# Xilinx_pwr.net
KiCad netlist of a schematic drawn in Altium Designer
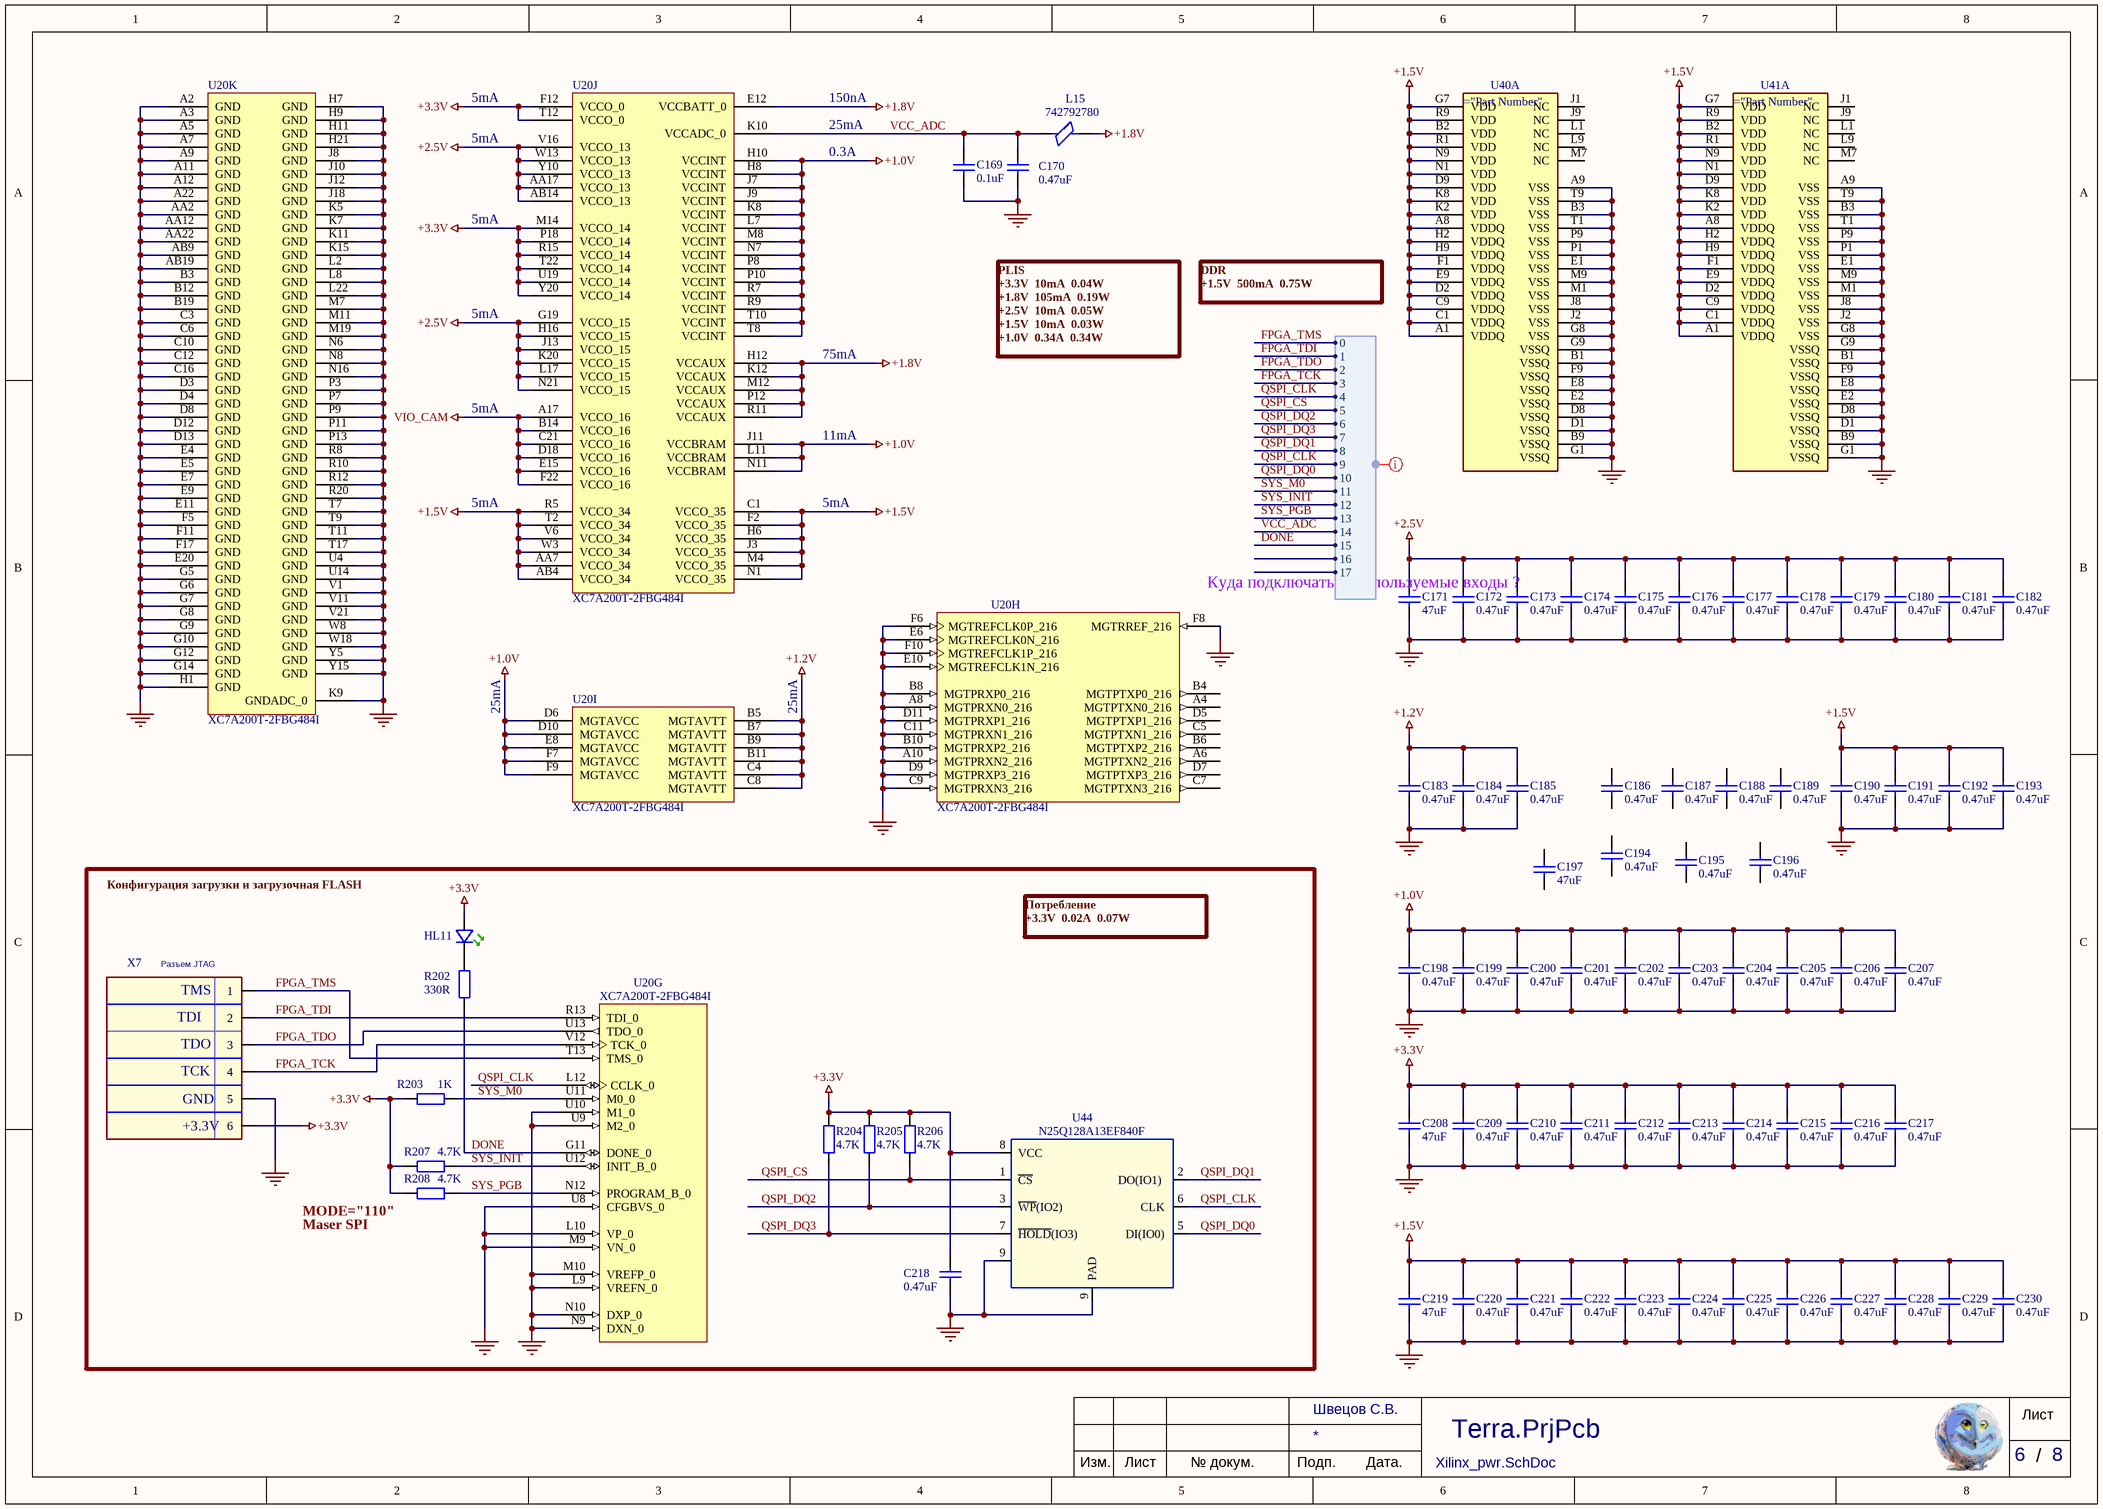
[diagram p0: Xilinx_pwr.SchDoc]

(export (version "E")
  (design (tool "Eeschema 10.0.6"))
  (components
    (comp (ref "C169")
      (value "0.1uF")
      (footprint "C0402")
      (description "Конденсатор керамический")
      (fields (field (name "VOLTAGE") "25V") (field (name "Comment") "Cap"))
      (libsource (lib "Terra") (part "Cap"))
    )
    (comp (ref "C170")
      (value "0.47uF")
      (footprint "C0402")
      (description "Конденсатор керамический")
      (fields (field (name "VOLTAGE") "10V") (field (name "Comment") "Cap"))
      (libsource (lib "Terra") (part "Cap"))
    )
    (comp (ref "C171")
      (value "47uF")
      (footprint "C0805")
      (description "C0805C476M9PAC")
      (fields (field (name "VOLTAGE") "6.3V") (field (name "Comment") "Cap"))
      (libsource (lib "Terra") (part "Cap"))
    )
    (comp (ref "C172")
      (value "0.47uF")
      (footprint "C0402")
      (description "Конденсатор керамический")
      (fields (field (name "VOLTAGE") "10V") (field (name "Comment") "Cap"))
      (libsource (lib "Terra") (part "Cap"))
    )
    (comp (ref "C173")
      (value "0.47uF")
      (footprint "C0402")
      (description "Конденсатор керамический")
      (fields (field (name "VOLTAGE") "10V") (field (name "Comment") "Cap"))
      (libsource (lib "Terra") (part "Cap"))
    )
    (comp (ref "C174")
      (value "0.47uF")
      (footprint "C0402")
      (description "Конденсатор керамический")
      (fields (field (name "VOLTAGE") "10V") (field (name "Comment") "Cap"))
      (libsource (lib "Terra") (part "Cap"))
    )
    (comp (ref "C175")
      (value "0.47uF")
      (footprint "C0402")
      (description "Конденсатор керамический")
      (fields (field (name "VOLTAGE") "10V") (field (name "Comment") "Cap"))
      (libsource (lib "Terra") (part "Cap"))
    )
    (comp (ref "C176")
      (value "0.47uF")
      (footprint "C0402")
      (description "Конденсатор керамический")
      (fields (field (name "VOLTAGE") "10V") (field (name "Comment") "Cap"))
      (libsource (lib "Terra") (part "Cap"))
    )
    (comp (ref "C177")
      (value "0.47uF")
      (footprint "C0402")
      (description "Конденсатор керамический")
      (fields (field (name "VOLTAGE") "10V") (field (name "Comment") "Cap"))
      (libsource (lib "Terra") (part "Cap"))
    )
    (comp (ref "C178")
      (value "0.47uF")
      (footprint "C0402")
      (description "Конденсатор керамический")
      (fields (field (name "VOLTAGE") "10V") (field (name "Comment") "Cap"))
      (libsource (lib "Terra") (part "Cap"))
    )
    (comp (ref "C179")
      (value "0.47uF")
      (footprint "C0402")
      (description "Конденсатор керамический")
      (fields (field (name "VOLTAGE") "10V") (field (name "Comment") "Cap"))
      (libsource (lib "Terra") (part "Cap"))
    )
    (comp (ref "C180")
      (value "0.47uF")
      (footprint "C0402")
      (description "Конденсатор керамический")
      (fields (field (name "VOLTAGE") "10V") (field (name "Comment") "Cap"))
      (libsource (lib "Terra") (part "Cap"))
    )
    (comp (ref "C181")
      (value "0.47uF")
      (footprint "C0402")
      (description "Конденсатор керамический")
      (fields (field (name "VOLTAGE") "10V") (field (name "Comment") "Cap"))
      (libsource (lib "Terra") (part "Cap"))
    )
    (comp (ref "C182")
      (value "0.47uF")
      (footprint "C0402")
      (description "Конденсатор керамический")
      (fields (field (name "VOLTAGE") "10V") (field (name "Comment") "Cap"))
      (libsource (lib "Terra") (part "Cap"))
    )
    (comp (ref "C183")
      (value "0.47uF")
      (footprint "C0402")
      (description "Конденсатор керамический")
      (fields (field (name "VOLTAGE") "10V") (field (name "Comment") "Cap"))
      (libsource (lib "Terra") (part "Cap"))
    )
    (comp (ref "C184")
      (value "0.47uF")
      (footprint "C0402")
      (description "Конденсатор керамический")
      (fields (field (name "VOLTAGE") "10V") (field (name "Comment") "Cap"))
      (libsource (lib "Terra") (part "Cap"))
    )
    (comp (ref "C185")
      (value "0.47uF")
      (footprint "C0402")
      (description "Конденсатор керамический")
      (fields (field (name "VOLTAGE") "10V") (field (name "Comment") "Cap"))
      (libsource (lib "Terra") (part "Cap"))
    )
    (comp (ref "C186")
      (value "0.47uF")
      (footprint "C0402")
      (description "Конденсатор керамический")
      (fields (field (name "VOLTAGE") "10V") (field (name "Comment") "Cap"))
      (libsource (lib "Terra") (part "Cap"))
    )
    (comp (ref "C187")
      (value "0.47uF")
      (footprint "C0402")
      (description "Конденсатор керамический")
      (fields (field (name "VOLTAGE") "10V") (field (name "Comment") "Cap"))
      (libsource (lib "Terra") (part "Cap"))
    )
    (comp (ref "C188")
      (value "0.47uF")
      (footprint "C0402")
      (description "Конденсатор керамический")
      (fields (field (name "VOLTAGE") "10V") (field (name "Comment") "Cap"))
      (libsource (lib "Terra") (part "Cap"))
    )
    (comp (ref "C189")
      (value "0.47uF")
      (footprint "C0402")
      (description "Конденсатор керамический")
      (fields (field (name "VOLTAGE") "10V") (field (name "Comment") "Cap"))
      (libsource (lib "Terra") (part "Cap"))
    )
    (comp (ref "C190")
      (value "0.47uF")
      (footprint "C0402")
      (description "Конденсатор керамический")
      (fields (field (name "VOLTAGE") "10V") (field (name "Comment") "Cap"))
      (libsource (lib "Terra") (part "Cap"))
    )
    (comp (ref "C191")
      (value "0.47uF")
      (footprint "C0402")
      (description "Конденсатор керамический")
      (fields (field (name "VOLTAGE") "10V") (field (name "Comment") "Cap"))
      (libsource (lib "Terra") (part "Cap"))
    )
    (comp (ref "C192")
      (value "0.47uF")
      (footprint "C0402")
      (description "Конденсатор керамический")
      (fields (field (name "VOLTAGE") "10V") (field (name "Comment") "Cap"))
      (libsource (lib "Terra") (part "Cap"))
    )
    (comp (ref "C193")
      (value "0.47uF")
      (footprint "C0402")
      (description "Конденсатор керамический")
      (fields (field (name "VOLTAGE") "10V") (field (name "Comment") "Cap"))
      (libsource (lib "Terra") (part "Cap"))
    )
    (comp (ref "C194")
      (value "0.47uF")
      (footprint "C0402")
      (description "Конденсатор керамический")
      (fields (field (name "VOLTAGE") "10V") (field (name "Comment") "Cap"))
      (libsource (lib "Terra") (part "Cap"))
    )
    (comp (ref "C195")
      (value "0.47uF")
      (footprint "C0402")
      (description "Конденсатор керамический")
      (fields (field (name "VOLTAGE") "10V") (field (name "Comment") "Cap"))
      (libsource (lib "Terra") (part "Cap"))
    )
    (comp (ref "C196")
      (value "0.47uF")
      (footprint "C0402")
      (description "Конденсатор керамический")
      (fields (field (name "VOLTAGE") "10V") (field (name "Comment") "Cap"))
      (libsource (lib "Terra") (part "Cap"))
    )
    (comp (ref "C197")
      (value "47uF")
      (footprint "C0805")
      (description "C0805C476M9PAC")
      (fields (field (name "VOLTAGE") "6.3V") (field (name "Comment") "Cap"))
      (libsource (lib "Terra") (part "Cap"))
    )
    (comp (ref "C198")
      (value "0.47uF")
      (footprint "C0402")
      (description "Конденсатор керамический")
      (fields (field (name "VOLTAGE") "10V") (field (name "Comment") "Cap"))
      (libsource (lib "Terra") (part "Cap"))
    )
    (comp (ref "C199")
      (value "0.47uF")
      (footprint "C0402")
      (description "Конденсатор керамический")
      (fields (field (name "VOLTAGE") "10V") (field (name "Comment") "Cap"))
      (libsource (lib "Terra") (part "Cap"))
    )
    (comp (ref "C200")
      (value "0.47uF")
      (footprint "C0402")
      (description "Конденсатор керамический")
      (fields (field (name "VOLTAGE") "10V") (field (name "Comment") "Cap"))
      (libsource (lib "Terra") (part "Cap"))
    )
    (comp (ref "C201")
      (value "0.47uF")
      (footprint "C0402")
      (description "Конденсатор керамический")
      (fields (field (name "VOLTAGE") "10V") (field (name "Comment") "Cap"))
      (libsource (lib "Terra") (part "Cap"))
    )
    (comp (ref "C202")
      (value "0.47uF")
      (footprint "C0402")
      (description "Конденсатор керамический")
      (fields (field (name "VOLTAGE") "10V") (field (name "Comment") "Cap"))
      (libsource (lib "Terra") (part "Cap"))
    )
    (comp (ref "C203")
      (value "0.47uF")
      (footprint "C0402")
      (description "Конденсатор керамический")
      (fields (field (name "VOLTAGE") "10V") (field (name "Comment") "Cap"))
      (libsource (lib "Terra") (part "Cap"))
    )
    (comp (ref "C204")
      (value "0.47uF")
      (footprint "C0402")
      (description "Конденсатор керамический")
      (fields (field (name "VOLTAGE") "10V") (field (name "Comment") "Cap"))
      (libsource (lib "Terra") (part "Cap"))
    )
    (comp (ref "C205")
      (value "0.47uF")
      (footprint "C0402")
      (description "Конденсатор керамический")
      (fields (field (name "VOLTAGE") "10V") (field (name "Comment") "Cap"))
      (libsource (lib "Terra") (part "Cap"))
    )
    (comp (ref "C206")
      (value "0.47uF")
      (footprint "C0402")
      (description "Конденсатор керамический")
      (fields (field (name "VOLTAGE") "10V") (field (name "Comment") "Cap"))
      (libsource (lib "Terra") (part "Cap"))
    )
    (comp (ref "C207")
      (value "0.47uF")
      (footprint "C0402")
      (description "Конденсатор керамический")
      (fields (field (name "VOLTAGE") "10V") (field (name "Comment") "Cap"))
      (libsource (lib "Terra") (part "Cap"))
    )
    (comp (ref "C208")
      (value "47uF")
      (footprint "C0805")
      (description "C0805C476M9PAC")
      (fields (field (name "VOLTAGE") "6.3V") (field (name "Comment") "Cap"))
      (libsource (lib "Terra") (part "Cap"))
    )
    (comp (ref "C209")
      (value "0.47uF")
      (footprint "C0402")
      (description "Конденсатор керамический")
      (fields (field (name "VOLTAGE") "10V") (field (name "Comment") "Cap"))
      (libsource (lib "Terra") (part "Cap"))
    )
    (comp (ref "C210")
      (value "0.47uF")
      (footprint "C0402")
      (description "Конденсатор керамический")
      (fields (field (name "VOLTAGE") "10V") (field (name "Comment") "Cap"))
      (libsource (lib "Terra") (part "Cap"))
    )
    (comp (ref "C211")
      (value "0.47uF")
      (footprint "C0402")
      (description "Конденсатор керамический")
      (fields (field (name "VOLTAGE") "10V") (field (name "Comment") "Cap"))
      (libsource (lib "Terra") (part "Cap"))
    )
    (comp (ref "C212")
      (value "0.47uF")
      (footprint "C0402")
      (description "Конденсатор керамический")
      (fields (field (name "VOLTAGE") "10V") (field (name "Comment") "Cap"))
      (libsource (lib "Terra") (part "Cap"))
    )
    (comp (ref "C213")
      (value "0.47uF")
      (footprint "C0402")
      (description "Конденсатор керамический")
      (fields (field (name "VOLTAGE") "10V") (field (name "Comment") "Cap"))
      (libsource (lib "Terra") (part "Cap"))
    )
    (comp (ref "C214")
      (value "0.47uF")
      (footprint "C0402")
      (description "Конденсатор керамический")
      (fields (field (name "VOLTAGE") "10V") (field (name "Comment") "Cap"))
      (libsource (lib "Terra") (part "Cap"))
    )
    (comp (ref "C215")
      (value "0.47uF")
      (footprint "C0402")
      (description "Конденсатор керамический")
      (fields (field (name "VOLTAGE") "10V") (field (name "Comment") "Cap"))
      (libsource (lib "Terra") (part "Cap"))
    )
    (comp (ref "C216")
      (value "0.47uF")
      (footprint "C0402")
      (description "Конденсатор керамический")
      (fields (field (name "VOLTAGE") "10V") (field (name "Comment") "Cap"))
      (libsource (lib "Terra") (part "Cap"))
    )
    (comp (ref "C217")
      (value "0.47uF")
      (footprint "C0402")
      (description "Конденсатор керамический")
      (fields (field (name "VOLTAGE") "10V") (field (name "Comment") "Cap"))
      (libsource (lib "Terra") (part "Cap"))
    )
    (comp (ref "C218")
      (value "0.47uF")
      (footprint "C0402")
      (description "Конденсатор керамический")
      (fields (field (name "VOLTAGE") "10V") (field (name "Comment") "Cap"))
      (libsource (lib "Terra") (part "Cap"))
    )
    (comp (ref "C219")
      (value "47uF")
      (footprint "C0805")
      (description "C0805C476M9PAC")
      (fields (field (name "VOLTAGE") "6.3V") (field (name "Comment") "Cap"))
      (libsource (lib "Terra") (part "Cap"))
    )
    (comp (ref "C220")
      (value "0.47uF")
      (footprint "C0402")
      (description "Конденсатор керамический")
      (fields (field (name "VOLTAGE") "10V") (field (name "Comment") "Cap"))
      (libsource (lib "Terra") (part "Cap"))
    )
    (comp (ref "C221")
      (value "0.47uF")
      (footprint "C0402")
      (description "Конденсатор керамический")
      (fields (field (name "VOLTAGE") "10V") (field (name "Comment") "Cap"))
      (libsource (lib "Terra") (part "Cap"))
    )
    (comp (ref "C222")
      (value "0.47uF")
      (footprint "C0402")
      (description "Конденсатор керамический")
      (fields (field (name "VOLTAGE") "10V") (field (name "Comment") "Cap"))
      (libsource (lib "Terra") (part "Cap"))
    )
    (comp (ref "C223")
      (value "0.47uF")
      (footprint "C0402")
      (description "Конденсатор керамический")
      (fields (field (name "VOLTAGE") "10V") (field (name "Comment") "Cap"))
      (libsource (lib "Terra") (part "Cap"))
    )
    (comp (ref "C224")
      (value "0.47uF")
      (footprint "C0402")
      (description "Конденсатор керамический")
      (fields (field (name "VOLTAGE") "10V") (field (name "Comment") "Cap"))
      (libsource (lib "Terra") (part "Cap"))
    )
    (comp (ref "C225")
      (value "0.47uF")
      (footprint "C0402")
      (description "Конденсатор керамический")
      (fields (field (name "VOLTAGE") "10V") (field (name "Comment") "Cap"))
      (libsource (lib "Terra") (part "Cap"))
    )
    (comp (ref "C226")
      (value "0.47uF")
      (footprint "C0402")
      (description "Конденсатор керамический")
      (fields (field (name "VOLTAGE") "10V") (field (name "Comment") "Cap"))
      (libsource (lib "Terra") (part "Cap"))
    )
    (comp (ref "C227")
      (value "0.47uF")
      (footprint "C0402")
      (description "Конденсатор керамический")
      (fields (field (name "VOLTAGE") "10V") (field (name "Comment") "Cap"))
      (libsource (lib "Terra") (part "Cap"))
    )
    (comp (ref "C228")
      (value "0.47uF")
      (footprint "C0402")
      (description "Конденсатор керамический")
      (fields (field (name "VOLTAGE") "10V") (field (name "Comment") "Cap"))
      (libsource (lib "Terra") (part "Cap"))
    )
    (comp (ref "C229")
      (value "0.47uF")
      (footprint "C0402")
      (description "Конденсатор керамический")
      (fields (field (name "VOLTAGE") "10V") (field (name "Comment") "Cap"))
      (libsource (lib "Terra") (part "Cap"))
    )
    (comp (ref "C230")
      (value "0.47uF")
      (footprint "C0402")
      (description "Конденсатор керамический")
      (fields (field (name "VOLTAGE") "10V") (field (name "Comment") "Cap"))
      (libsource (lib "Terra") (part "Cap"))
    )
    (comp (ref "HL11")
      (value "~")
      (footprint "KP-1608_16x08x11_L")
      (description "1.6X0.8mm SMD  LED")
      (libsource (lib "Terra") (part "ledG_KP-1608MGC_KP-1608"))
    )
    (comp (ref "L15")
      (value "742792780")
      (footprint "L0402")
      (description "Wurth Elektronik EMI FILTERS FERRITE BEAD, 220R@100MHz, 0.35R")
      (libsource (lib "Terra") (part "BEAD_FERRITE_SM"))
    )
    (comp (ref "R202")
      (value "330R")
      (footprint "R0402")
      (description "Резистор")
      (fields (field (name "Comment") "Res2"))
      (libsource (lib "Terra") (part "Res2"))
    )
    (comp (ref "R203")
      (value "1K")
      (footprint "R0402")
      (description "Резистор")
      (fields (field (name "Comment") "Res2"))
      (libsource (lib "") (part "Res2_1"))
    )
    (comp (ref "R204")
      (value "4.7K")
      (footprint "R0402")
      (description "Резистор")
      (fields (field (name "Comment") "Res2"))
      (libsource (lib "Terra") (part "Res2"))
    )
    (comp (ref "R205")
      (value "4.7K")
      (footprint "R0402")
      (description "Резистор")
      (fields (field (name "Comment") "Res2"))
      (libsource (lib "Terra") (part "Res2"))
    )
    (comp (ref "R206")
      (value "4.7K")
      (footprint "R0402")
      (description "Резистор")
      (fields (field (name "Comment") "Res2"))
      (libsource (lib "Terra") (part "Res2"))
    )
    (comp (ref "R207")
      (value "4.7K")
      (footprint "R0402")
      (description "Резистор")
      (fields (field (name "Comment") "Res2"))
      (libsource (lib "") (part "Res2_1"))
    )
    (comp (ref "R208")
      (value "4.7K")
      (footprint "R0402")
      (description "Резистор")
      (fields (field (name "Comment") "Res2"))
      (libsource (lib "") (part "Res2_1"))
    )
    (comp (ref "U20")
      (value "XC7A200T-2FBG484I")
      (footprint "FBG484")
      (description "Artix-7 FPGA, 285 User I/Os, 4 GTP, 484-Ball BGA")
      (fields (field (name "MANUFACTURER") "Xilinx") (field (name "GENERIC PART NUMBER") "XC7A200T"))
      (libsource (lib "Terra") (part "XC7A200T-2FBG484I"))
    )
    (comp (ref "U40")
      (value "MT41J256M16HA-125-E")
      (footprint "FBGA96_9X14_MRN")
      (description "DDR3 SDRAM 32Meg x 16 x 8 banks")
      (libsource (lib "Terra") (part "MT41J256M16HA-125-E"))
    )
    (comp (ref "U41")
      (value "MT41J256M16HA-125-E")
      (footprint "FBGA96_9X14_MRN")
      (description "DDR3 SDRAM 32Meg x 16 x 8 banks")
      (libsource (lib "Terra") (part "MT41J256M16HA-125-E"))
    )
    (comp (ref "U44")
      (value "N25Q128A13EF840F")
      (footprint "VPDFN8_8X6_MRN-L")
      (description "Serial NOR Flash 128Mb 3V")
      (libsource (lib "Terra") (part "N25Q128A13EF840F"))
    )
    (comp (ref "X7") (value "Разъем JTAG") (footprint "HEADER-1X6S") (libsource (lib "*") (part "CON1x6")))
  )
  (nets
    (net (code "1") (name "+1.0V") (class "Default")
      (node (ref "C198") (pin "1") (pinfunction "1_1") (pintype "passive"))
      (node (ref "C199") (pin "1") (pinfunction "1_1") (pintype "passive"))
      (node (ref "C200") (pin "1") (pinfunction "1_1") (pintype "passive"))
      (node (ref "C201") (pin "1") (pinfunction "1_1") (pintype "passive"))
      (node (ref "C202") (pin "1") (pinfunction "1_1") (pintype "passive"))
      (node (ref "C203") (pin "1") (pinfunction "1_1") (pintype "passive"))
      (node (ref "C204") (pin "1") (pinfunction "1_1") (pintype "passive"))
      (node (ref "C205") (pin "1") (pinfunction "1_1") (pintype "passive"))
      (node (ref "C206") (pin "1") (pinfunction "1_1") (pintype "passive"))
      (node (ref "C207") (pin "1") (pinfunction "1_1") (pintype "passive"))
      (node (ref "U20") (pin "D10") (pinfunction "MGTAVCC_D10") (pintype "power_in"))
      (node (ref "U20") (pin "D6") (pinfunction "MGTAVCC_D6") (pintype "power_in"))
      (node (ref "U20") (pin "E8") (pinfunction "MGTAVCC_E8") (pintype "power_in"))
      (node (ref "U20") (pin "F7") (pinfunction "MGTAVCC_F7") (pintype "power_in"))
      (node (ref "U20") (pin "F9") (pinfunction "MGTAVCC_F9") (pintype "power_in"))
      (node (ref "U20") (pin "H10") (pinfunction "VCCINT_H10") (pintype "power_in"))
      (node (ref "U20") (pin "H8") (pinfunction "VCCINT_H8") (pintype "power_in"))
      (node (ref "U20") (pin "J11") (pinfunction "VCCBRAM_J11") (pintype "power_in"))
      (node (ref "U20") (pin "J7") (pinfunction "VCCINT_J7") (pintype "power_in"))
      (node (ref "U20") (pin "J9") (pinfunction "VCCINT_J9") (pintype "power_in"))
      (node (ref "U20") (pin "K8") (pinfunction "VCCINT_K8") (pintype "power_in"))
      (node (ref "U20") (pin "L11") (pinfunction "VCCBRAM_L11") (pintype "power_in"))
      (node (ref "U20") (pin "L7") (pinfunction "VCCINT_L7") (pintype "power_in"))
      (node (ref "U20") (pin "M8") (pinfunction "VCCINT_M8") (pintype "power_in"))
      (node (ref "U20") (pin "N11") (pinfunction "VCCBRAM_N11") (pintype "power_in"))
      (node (ref "U20") (pin "N7") (pinfunction "VCCINT_N7") (pintype "power_in"))
      (node (ref "U20") (pin "P10") (pinfunction "VCCINT_P10") (pintype "power_in"))
      (node (ref "U20") (pin "P8") (pinfunction "VCCINT_P8") (pintype "power_in"))
      (node (ref "U20") (pin "R7") (pinfunction "VCCINT_R7") (pintype "power_in"))
      (node (ref "U20") (pin "R9") (pinfunction "VCCINT_R9") (pintype "power_in"))
      (node (ref "U20") (pin "T10") (pinfunction "VCCINT_T10") (pintype "power_in"))
      (node (ref "U20") (pin "T8") (pinfunction "VCCINT_T8") (pintype "power_in"))
    )
    (net (code "2") (name "+1.2V") (class "Default")
      (node (ref "C183") (pin "1") (pinfunction "1_1") (pintype "passive"))
      (node (ref "C184") (pin "1") (pinfunction "1_1") (pintype "passive"))
      (node (ref "C185") (pin "1") (pinfunction "1_1") (pintype "passive"))
      (node (ref "U20") (pin "B11") (pinfunction "MGTAVTT_B11") (pintype "power_in"))
      (node (ref "U20") (pin "B5") (pinfunction "MGTAVTT_B5") (pintype "power_in"))
      (node (ref "U20") (pin "B7") (pinfunction "MGTAVTT_B7") (pintype "power_in"))
      (node (ref "U20") (pin "B9") (pinfunction "MGTAVTT_B9") (pintype "power_in"))
      (node (ref "U20") (pin "C4") (pinfunction "MGTAVTT_C4") (pintype "power_in"))
      (node (ref "U20") (pin "C8") (pinfunction "MGTAVTT_C8") (pintype "power_in"))
    )
    (net (code "3") (name "+1.5V") (class "Default")
      (node (ref "C190") (pin "1") (pinfunction "1_1") (pintype "passive"))
      (node (ref "C191") (pin "1") (pinfunction "1_1") (pintype "passive"))
      (node (ref "C192") (pin "1") (pinfunction "1_1") (pintype "passive"))
      (node (ref "C193") (pin "1") (pinfunction "1_1") (pintype "passive"))
      (node (ref "C219") (pin "1") (pinfunction "1_1") (pintype "passive"))
      (node (ref "C220") (pin "1") (pinfunction "1_1") (pintype "passive"))
      (node (ref "C221") (pin "1") (pinfunction "1_1") (pintype "passive"))
      (node (ref "C222") (pin "1") (pinfunction "1_1") (pintype "passive"))
      (node (ref "C223") (pin "1") (pinfunction "1_1") (pintype "passive"))
      (node (ref "C224") (pin "1") (pinfunction "1_1") (pintype "passive"))
      (node (ref "C225") (pin "1") (pinfunction "1_1") (pintype "passive"))
      (node (ref "C226") (pin "1") (pinfunction "1_1") (pintype "passive"))
      (node (ref "C227") (pin "1") (pinfunction "1_1") (pintype "passive"))
      (node (ref "C228") (pin "1") (pinfunction "1_1") (pintype "passive"))
      (node (ref "C229") (pin "1") (pinfunction "1_1") (pintype "passive"))
      (node (ref "C230") (pin "1") (pinfunction "1_1") (pintype "passive"))
      (node (ref "U20") (pin "AA7") (pinfunction "VCCO_34_AA7") (pintype "power_in"))
      (node (ref "U20") (pin "AB4") (pinfunction "VCCO_34_AB4") (pintype "power_in"))
      (node (ref "U20") (pin "C1") (pinfunction "VCCO_35_C1") (pintype "power_in"))
      (node (ref "U20") (pin "F2") (pinfunction "VCCO_35_F2") (pintype "power_in"))
      (node (ref "U20") (pin "H6") (pinfunction "VCCO_35_H6") (pintype "power_in"))
      (node (ref "U20") (pin "J3") (pinfunction "VCCO_35_J3") (pintype "power_in"))
      (node (ref "U20") (pin "M4") (pinfunction "VCCO_35_M4") (pintype "power_in"))
      (node (ref "U20") (pin "N1") (pinfunction "VCCO_35_N1") (pintype "power_in"))
      (node (ref "U20") (pin "R5") (pinfunction "VCCO_34_R5") (pintype "power_in"))
      (node (ref "U20") (pin "T2") (pinfunction "VCCO_34_T2") (pintype "power_in"))
      (node (ref "U20") (pin "V6") (pinfunction "VCCO_34_V6") (pintype "power_in"))
      (node (ref "U20") (pin "W3") (pinfunction "VCCO_34_W3") (pintype "power_in"))
      (node (ref "U40") (pin "A1") (pinfunction "VDDQ_A1") (pintype "power_in"))
      (node (ref "U40") (pin "A8") (pinfunction "VDDQ_A8") (pintype "power_in"))
      (node (ref "U40") (pin "B2") (pinfunction "VDD_B2") (pintype "power_in"))
      (node (ref "U40") (pin "C1") (pinfunction "VDDQ_C1") (pintype "power_in"))
      (node (ref "U40") (pin "C9") (pinfunction "VDDQ_C9") (pintype "power_in"))
      (node (ref "U40") (pin "D2") (pinfunction "VDDQ_D2") (pintype "power_in"))
      (node (ref "U40") (pin "D9") (pinfunction "VDD_D9") (pintype "power_in"))
      (node (ref "U40") (pin "E9") (pinfunction "VDDQ_E9") (pintype "power_in"))
      (node (ref "U40") (pin "F1") (pinfunction "VDDQ_F1") (pintype "power_in"))
      (node (ref "U40") (pin "G7") (pinfunction "VDD_G7") (pintype "power_in"))
      (node (ref "U40") (pin "H2") (pinfunction "VDDQ_H2") (pintype "power_in"))
      (node (ref "U40") (pin "H9") (pinfunction "VDDQ_H9") (pintype "power_in"))
      (node (ref "U40") (pin "K2") (pinfunction "VDD_K2") (pintype "power_in"))
      (node (ref "U40") (pin "K8") (pinfunction "VDD_K8") (pintype "power_in"))
      (node (ref "U40") (pin "N1") (pinfunction "VDD_N1") (pintype "power_in"))
      (node (ref "U40") (pin "N9") (pinfunction "VDD_N9") (pintype "power_in"))
      (node (ref "U40") (pin "R1") (pinfunction "VDD_R1") (pintype "power_in"))
      (node (ref "U40") (pin "R9") (pinfunction "VDD_R9") (pintype "power_in"))
      (node (ref "U41") (pin "A1") (pinfunction "VDDQ_A1") (pintype "power_in"))
      (node (ref "U41") (pin "A8") (pinfunction "VDDQ_A8") (pintype "power_in"))
      (node (ref "U41") (pin "B2") (pinfunction "VDD_B2") (pintype "power_in"))
      (node (ref "U41") (pin "C1") (pinfunction "VDDQ_C1") (pintype "power_in"))
      (node (ref "U41") (pin "C9") (pinfunction "VDDQ_C9") (pintype "power_in"))
      (node (ref "U41") (pin "D2") (pinfunction "VDDQ_D2") (pintype "power_in"))
      (node (ref "U41") (pin "D9") (pinfunction "VDD_D9") (pintype "power_in"))
      (node (ref "U41") (pin "E9") (pinfunction "VDDQ_E9") (pintype "power_in"))
      (node (ref "U41") (pin "F1") (pinfunction "VDDQ_F1") (pintype "power_in"))
      (node (ref "U41") (pin "G7") (pinfunction "VDD_G7") (pintype "power_in"))
      (node (ref "U41") (pin "H2") (pinfunction "VDDQ_H2") (pintype "power_in"))
      (node (ref "U41") (pin "H9") (pinfunction "VDDQ_H9") (pintype "power_in"))
      (node (ref "U41") (pin "K2") (pinfunction "VDD_K2") (pintype "power_in"))
      (node (ref "U41") (pin "K8") (pinfunction "VDD_K8") (pintype "power_in"))
      (node (ref "U41") (pin "N1") (pinfunction "VDD_N1") (pintype "power_in"))
      (node (ref "U41") (pin "N9") (pinfunction "VDD_N9") (pintype "power_in"))
      (node (ref "U41") (pin "R1") (pinfunction "VDD_R1") (pintype "power_in"))
      (node (ref "U41") (pin "R9") (pinfunction "VDD_R9") (pintype "power_in"))
    )
    (net (code "4") (name "+1.8V") (class "Default")
      (node (ref "L15") (pin "2") (pinfunction "2_2") (pintype "passive"))
      (node (ref "U20") (pin "E12") (pinfunction "VCCBATT_0_E12") (pintype "power_in"))
      (node (ref "U20") (pin "H12") (pinfunction "VCCAUX_H12") (pintype "power_in"))
      (node (ref "U20") (pin "K12") (pinfunction "VCCAUX_K12") (pintype "power_in"))
      (node (ref "U20") (pin "M12") (pinfunction "VCCAUX_M12") (pintype "power_in"))
      (node (ref "U20") (pin "P12") (pinfunction "VCCAUX_P12") (pintype "power_in"))
      (node (ref "U20") (pin "R11") (pinfunction "VCCAUX_R11") (pintype "power_in"))
    )
    (net (code "5") (name "+2.5V") (class "Default")
      (node (ref "C171") (pin "1") (pinfunction "1_1") (pintype "passive"))
      (node (ref "C172") (pin "1") (pinfunction "1_1") (pintype "passive"))
      (node (ref "C173") (pin "1") (pinfunction "1_1") (pintype "passive"))
      (node (ref "C174") (pin "1") (pinfunction "1_1") (pintype "passive"))
      (node (ref "C175") (pin "1") (pinfunction "1_1") (pintype "passive"))
      (node (ref "C176") (pin "1") (pinfunction "1_1") (pintype "passive"))
      (node (ref "C177") (pin "1") (pinfunction "1_1") (pintype "passive"))
      (node (ref "C178") (pin "1") (pinfunction "1_1") (pintype "passive"))
      (node (ref "C179") (pin "1") (pinfunction "1_1") (pintype "passive"))
      (node (ref "C180") (pin "1") (pinfunction "1_1") (pintype "passive"))
      (node (ref "C181") (pin "1") (pinfunction "1_1") (pintype "passive"))
      (node (ref "C182") (pin "1") (pinfunction "1_1") (pintype "passive"))
      (node (ref "U20") (pin "AA17") (pinfunction "VCCO_13_AA17") (pintype "power_in"))
      (node (ref "U20") (pin "AB14") (pinfunction "VCCO_13_AB14") (pintype "power_in"))
      (node (ref "U20") (pin "G19") (pinfunction "VCCO_15_G19") (pintype "power_in"))
      (node (ref "U20") (pin "H16") (pinfunction "VCCO_15_H16") (pintype "power_in"))
      (node (ref "U20") (pin "J13") (pinfunction "VCCO_15_J13") (pintype "power_in"))
      (node (ref "U20") (pin "K20") (pinfunction "VCCO_15_K20") (pintype "power_in"))
      (node (ref "U20") (pin "L17") (pinfunction "VCCO_15_L17") (pintype "power_in"))
      (node (ref "U20") (pin "N21") (pinfunction "VCCO_15_N21") (pintype "power_in"))
      (node (ref "U20") (pin "V16") (pinfunction "VCCO_13_V16") (pintype "power_in"))
      (node (ref "U20") (pin "W13") (pinfunction "VCCO_13_W13") (pintype "power_in"))
      (node (ref "U20") (pin "Y10") (pinfunction "VCCO_13_Y10") (pintype "power_in"))
    )
    (net (code "6") (name "+3.3V") (class "Default")
      (node (ref "C208") (pin "1") (pinfunction "1_1") (pintype "passive"))
      (node (ref "C209") (pin "1") (pinfunction "1_1") (pintype "passive"))
      (node (ref "C210") (pin "1") (pinfunction "1_1") (pintype "passive"))
      (node (ref "C211") (pin "1") (pinfunction "1_1") (pintype "passive"))
      (node (ref "C212") (pin "1") (pinfunction "1_1") (pintype "passive"))
      (node (ref "C213") (pin "1") (pinfunction "1_1") (pintype "passive"))
      (node (ref "C214") (pin "1") (pinfunction "1_1") (pintype "passive"))
      (node (ref "C215") (pin "1") (pinfunction "1_1") (pintype "passive"))
      (node (ref "C216") (pin "1") (pinfunction "1_1") (pintype "passive"))
      (node (ref "C217") (pin "1") (pinfunction "1_1") (pintype "passive"))
      (node (ref "C218") (pin "1") (pinfunction "1_1") (pintype "passive"))
      (node (ref "HL11") (pin "1") (pinfunction "Anode_1") (pintype "passive"))
      (node (ref "R203") (pin "1") (pinfunction "1_1") (pintype "passive"))
      (node (ref "R204") (pin "2") (pinfunction "2_2") (pintype "passive"))
      (node (ref "R205") (pin "2") (pinfunction "2_2") (pintype "passive"))
      (node (ref "R206") (pin "2") (pinfunction "2_2") (pintype "passive"))
      (node (ref "R207") (pin "1") (pinfunction "1_1") (pintype "passive"))
      (node (ref "R208") (pin "1") (pinfunction "1_1") (pintype "passive"))
      (node (ref "U20") (pin "F12") (pinfunction "VCCO_0_F12") (pintype "power_in"))
      (node (ref "U20") (pin "M14") (pinfunction "VCCO_14_M14") (pintype "power_in"))
      (node (ref "U20") (pin "P18") (pinfunction "VCCO_14_P18") (pintype "power_in"))
      (node (ref "U20") (pin "R15") (pinfunction "VCCO_14_R15") (pintype "power_in"))
      (node (ref "U20") (pin "T12") (pinfunction "VCCO_0_T12") (pintype "power_in"))
      (node (ref "U20") (pin "T22") (pinfunction "VCCO_14_T22") (pintype "power_in"))
      (node (ref "U20") (pin "U19") (pinfunction "VCCO_14_U19") (pintype "power_in"))
      (node (ref "U20") (pin "Y20") (pinfunction "VCCO_14_Y20") (pintype "power_in"))
      (node (ref "U44") (pin "8") (pinfunction "VCC_8") (pintype "power_in"))
      (node (ref "X7") (pin "6") (pinfunction "6_6") (pintype "passive"))
    )
    (net (code "7") (name "/DONE") (class "Default")
      (node (ref "R202") (pin "1") (pinfunction "1_1") (pintype "passive"))
      (node (ref "U20") (pin "G11") (pinfunction "DONE_0_G11") (pintype "bidirectional"))
    )
    (net (code "8") (name "/FPGA_TCK") (class "Default")
      (node (ref "U20") (pin "V12") (pinfunction "TCK_0_V12") (pintype "input"))
      (node (ref "X7") (pin "4") (pinfunction "4_4") (pintype "passive"))
    )
    (net (code "9") (name "/FPGA_TDI") (class "Default")
      (node (ref "U20") (pin "R13") (pinfunction "TDI_0_R13") (pintype "input"))
      (node (ref "X7") (pin "2") (pinfunction "2_2") (pintype "passive"))
    )
    (net (code "10") (name "/FPGA_TDO") (class "Default")
      (node (ref "U20") (pin "U13") (pinfunction "TDO_0_U13") (pintype "output"))
      (node (ref "X7") (pin "3") (pinfunction "3_3") (pintype "passive"))
    )
    (net (code "11") (name "/FPGA_TMS") (class "Default")
      (node (ref "U20") (pin "T13") (pinfunction "TMS_0_T13") (pintype "input"))
      (node (ref "X7") (pin "1") (pinfunction "1_1") (pintype "passive"))
    )
    (net (code "12") (name "/QSPI_CLK") (class "Default")
      (node (ref "U20") (pin "L12") (pinfunction "CCLK_0_L12") (pintype "bidirectional"))
      (node (ref "U44") (pin "6") (pinfunction "CLK_6") (pintype "passive"))
    )
    (net (code "13") (name "/QSPI_CS") (class "Default")
      (node (ref "R206") (pin "1") (pinfunction "1_1") (pintype "passive"))
      (node (ref "U44") (pin "1") (pinfunction "~{CS}_1") (pintype "passive"))
    )
    (net (code "14") (name "/QSPI_DQ0") (class "Default")
      (node (ref "U44") (pin "5") (pinfunction "DI(IO0)_5") (pintype "passive"))
    )
    (net (code "15") (name "/QSPI_DQ1") (class "Default")
      (node (ref "U44") (pin "2") (pinfunction "DO(IO1)_2") (pintype "passive"))
    )
    (net (code "16") (name "/QSPI_DQ2") (class "Default")
      (node (ref "R205") (pin "1") (pinfunction "1_1") (pintype "passive"))
      (node (ref "U44") (pin "3") (pinfunction "~{WP}(IO2)_3") (pintype "passive"))
    )
    (net (code "17") (name "/QSPI_DQ3") (class "Default")
      (node (ref "R204") (pin "1") (pinfunction "1_1") (pintype "passive"))
      (node (ref "U44") (pin "7") (pinfunction "~{HOLD}(IO3)_7") (pintype "passive"))
    )
    (net (code "18") (name "/SYS_INIT") (class "Default")
      (node (ref "R207") (pin "2") (pinfunction "2_2") (pintype "passive"))
      (node (ref "U20") (pin "U12") (pinfunction "INIT_B_0_U12") (pintype "bidirectional"))
    )
    (net (code "19") (name "/SYS_M0") (class "Default")
      (node (ref "R203") (pin "2") (pinfunction "2_2") (pintype "passive"))
      (node (ref "U20") (pin "U11") (pinfunction "M0_0_U11") (pintype "input"))
    )
    (net (code "20") (name "/SYS_PGB") (class "Default")
      (node (ref "R208") (pin "2") (pinfunction "2_2") (pintype "passive"))
      (node (ref "U20") (pin "N12") (pinfunction "PROGRAM_B_0_N12") (pintype "input"))
    )
    (net (code "21") (name "/VCC_ADC") (class "Default")
      (node (ref "C169") (pin "1") (pinfunction "1_1") (pintype "passive"))
      (node (ref "C170") (pin "1") (pinfunction "1_1") (pintype "passive"))
      (node (ref "L15") (pin "1") (pinfunction "1_1") (pintype "passive"))
      (node (ref "U20") (pin "K10") (pinfunction "VCCADC_0_K10") (pintype "power_in"))
    )
    (net (code "22") (name "GND") (class "Default")
      (node (ref "C169") (pin "2") (pinfunction "2_2") (pintype "passive"))
      (node (ref "C170") (pin "2") (pinfunction "2_2") (pintype "passive"))
      (node (ref "C171") (pin "2") (pinfunction "2_2") (pintype "passive"))
      (node (ref "C172") (pin "2") (pinfunction "2_2") (pintype "passive"))
      (node (ref "C173") (pin "2") (pinfunction "2_2") (pintype "passive"))
      (node (ref "C174") (pin "2") (pinfunction "2_2") (pintype "passive"))
      (node (ref "C175") (pin "2") (pinfunction "2_2") (pintype "passive"))
      (node (ref "C176") (pin "2") (pinfunction "2_2") (pintype "passive"))
      (node (ref "C177") (pin "2") (pinfunction "2_2") (pintype "passive"))
      (node (ref "C178") (pin "2") (pinfunction "2_2") (pintype "passive"))
      (node (ref "C179") (pin "2") (pinfunction "2_2") (pintype "passive"))
      (node (ref "C180") (pin "2") (pinfunction "2_2") (pintype "passive"))
      (node (ref "C181") (pin "2") (pinfunction "2_2") (pintype "passive"))
      (node (ref "C182") (pin "2") (pinfunction "2_2") (pintype "passive"))
      (node (ref "C183") (pin "2") (pinfunction "2_2") (pintype "passive"))
      (node (ref "C184") (pin "2") (pinfunction "2_2") (pintype "passive"))
      (node (ref "C185") (pin "2") (pinfunction "2_2") (pintype "passive"))
      (node (ref "C190") (pin "2") (pinfunction "2_2") (pintype "passive"))
      (node (ref "C191") (pin "2") (pinfunction "2_2") (pintype "passive"))
      (node (ref "C192") (pin "2") (pinfunction "2_2") (pintype "passive"))
      (node (ref "C193") (pin "2") (pinfunction "2_2") (pintype "passive"))
      (node (ref "C198") (pin "2") (pinfunction "2_2") (pintype "passive"))
      (node (ref "C199") (pin "2") (pinfunction "2_2") (pintype "passive"))
      (node (ref "C200") (pin "2") (pinfunction "2_2") (pintype "passive"))
      (node (ref "C201") (pin "2") (pinfunction "2_2") (pintype "passive"))
      (node (ref "C202") (pin "2") (pinfunction "2_2") (pintype "passive"))
      (node (ref "C203") (pin "2") (pinfunction "2_2") (pintype "passive"))
      (node (ref "C204") (pin "2") (pinfunction "2_2") (pintype "passive"))
      (node (ref "C205") (pin "2") (pinfunction "2_2") (pintype "passive"))
      (node (ref "C206") (pin "2") (pinfunction "2_2") (pintype "passive"))
      (node (ref "C207") (pin "2") (pinfunction "2_2") (pintype "passive"))
      (node (ref "C208") (pin "2") (pinfunction "2_2") (pintype "passive"))
      (node (ref "C209") (pin "2") (pinfunction "2_2") (pintype "passive"))
      (node (ref "C210") (pin "2") (pinfunction "2_2") (pintype "passive"))
      (node (ref "C211") (pin "2") (pinfunction "2_2") (pintype "passive"))
      (node (ref "C212") (pin "2") (pinfunction "2_2") (pintype "passive"))
      (node (ref "C213") (pin "2") (pinfunction "2_2") (pintype "passive"))
      (node (ref "C214") (pin "2") (pinfunction "2_2") (pintype "passive"))
      (node (ref "C215") (pin "2") (pinfunction "2_2") (pintype "passive"))
      (node (ref "C216") (pin "2") (pinfunction "2_2") (pintype "passive"))
      (node (ref "C217") (pin "2") (pinfunction "2_2") (pintype "passive"))
      (node (ref "C218") (pin "2") (pinfunction "2_2") (pintype "passive"))
      (node (ref "C219") (pin "2") (pinfunction "2_2") (pintype "passive"))
      (node (ref "C220") (pin "2") (pinfunction "2_2") (pintype "passive"))
      (node (ref "C221") (pin "2") (pinfunction "2_2") (pintype "passive"))
      (node (ref "C222") (pin "2") (pinfunction "2_2") (pintype "passive"))
      (node (ref "C223") (pin "2") (pinfunction "2_2") (pintype "passive"))
      (node (ref "C224") (pin "2") (pinfunction "2_2") (pintype "passive"))
      (node (ref "C225") (pin "2") (pinfunction "2_2") (pintype "passive"))
      (node (ref "C226") (pin "2") (pinfunction "2_2") (pintype "passive"))
      (node (ref "C227") (pin "2") (pinfunction "2_2") (pintype "passive"))
      (node (ref "C228") (pin "2") (pinfunction "2_2") (pintype "passive"))
      (node (ref "C229") (pin "2") (pinfunction "2_2") (pintype "passive"))
      (node (ref "C230") (pin "2") (pinfunction "2_2") (pintype "passive"))
      (node (ref "U20") (pin "A10") (pinfunction "MGTPRXN2_216_A10") (pintype "input"))
      (node (ref "U20") (pin "A11") (pinfunction "GND_A11") (pintype "power_in"))
      (node (ref "U20") (pin "A12") (pinfunction "GND_A12") (pintype "power_in"))
      (node (ref "U20") (pin "A2") (pinfunction "GND_A2") (pintype "power_in"))
      (node (ref "U20") (pin "A22") (pinfunction "GND_A22") (pintype "power_in"))
      (node (ref "U20") (pin "A3") (pinfunction "GND_A3") (pintype "power_in"))
      (node (ref "U20") (pin "A5") (pinfunction "GND_A5") (pintype "power_in"))
      (node (ref "U20") (pin "A7") (pinfunction "GND_A7") (pintype "power_in"))
      (node (ref "U20") (pin "A8") (pinfunction "MGTPRXN0_216_A8") (pintype "input"))
      (node (ref "U20") (pin "A9") (pinfunction "GND_A9") (pintype "power_in"))
      (node (ref "U20") (pin "AA12") (pinfunction "GND_AA12") (pintype "power_in"))
      (node (ref "U20") (pin "AA2") (pinfunction "GND_AA2") (pintype "power_in"))
      (node (ref "U20") (pin "AA22") (pinfunction "GND_AA22") (pintype "power_in"))
      (node (ref "U20") (pin "AB19") (pinfunction "GND_AB19") (pintype "power_in"))
      (node (ref "U20") (pin "AB9") (pinfunction "GND_AB9") (pintype "power_in"))
      (node (ref "U20") (pin "B10") (pinfunction "MGTPRXP2_216_B10") (pintype "input"))
      (node (ref "U20") (pin "B12") (pinfunction "GND_B12") (pintype "power_in"))
      (node (ref "U20") (pin "B19") (pinfunction "GND_B19") (pintype "power_in"))
      (node (ref "U20") (pin "B3") (pinfunction "GND_B3") (pintype "power_in"))
      (node (ref "U20") (pin "B8") (pinfunction "MGTPRXP0_216_B8") (pintype "input"))
      (node (ref "U20") (pin "C10") (pinfunction "GND_C10") (pintype "power_in"))
      (node (ref "U20") (pin "C11") (pinfunction "MGTPRXN1_216_C11") (pintype "input"))
      (node (ref "U20") (pin "C12") (pinfunction "GND_C12") (pintype "power_in"))
      (node (ref "U20") (pin "C16") (pinfunction "GND_C16") (pintype "power_in"))
      (node (ref "U20") (pin "C3") (pinfunction "GND_C3") (pintype "power_in"))
      (node (ref "U20") (pin "C6") (pinfunction "GND_C6") (pintype "power_in"))
      (node (ref "U20") (pin "C9") (pinfunction "MGTPRXN3_216_C9") (pintype "input"))
      (node (ref "U20") (pin "D11") (pinfunction "MGTPRXP1_216_D11") (pintype "input"))
      (node (ref "U20") (pin "D12") (pinfunction "GND_D12") (pintype "power_in"))
      (node (ref "U20") (pin "D13") (pinfunction "GND_D13") (pintype "power_in"))
      (node (ref "U20") (pin "D3") (pinfunction "GND_D3") (pintype "power_in"))
      (node (ref "U20") (pin "D4") (pinfunction "GND_D4") (pintype "power_in"))
      (node (ref "U20") (pin "D8") (pinfunction "GND_D8") (pintype "power_in"))
      (node (ref "U20") (pin "D9") (pinfunction "MGTPRXP3_216_D9") (pintype "input"))
      (node (ref "U20") (pin "E10") (pinfunction "MGTREFCLK1N_216_E10") (pintype "input"))
      (node (ref "U20") (pin "E11") (pinfunction "GND_E11") (pintype "power_in"))
      (node (ref "U20") (pin "E20") (pinfunction "GND_E20") (pintype "power_in"))
      (node (ref "U20") (pin "E4") (pinfunction "GND_E4") (pintype "power_in"))
      (node (ref "U20") (pin "E5") (pinfunction "GND_E5") (pintype "power_in"))
      (node (ref "U20") (pin "E6") (pinfunction "MGTREFCLK0N_216_E6") (pintype "input"))
      (node (ref "U20") (pin "E7") (pinfunction "GND_E7") (pintype "power_in"))
      (node (ref "U20") (pin "E9") (pinfunction "GND_E9") (pintype "power_in"))
      (node (ref "U20") (pin "F10") (pinfunction "MGTREFCLK1P_216_F10") (pintype "input"))
      (node (ref "U20") (pin "F11") (pinfunction "GND_F11") (pintype "power_in"))
      (node (ref "U20") (pin "F17") (pinfunction "GND_F17") (pintype "power_in"))
      (node (ref "U20") (pin "F5") (pinfunction "GND_F5") (pintype "power_in"))
      (node (ref "U20") (pin "F6") (pinfunction "MGTREFCLK0P_216_F6") (pintype "input"))
      (node (ref "U20") (pin "F8") (pinfunction "MGTRREF_216_F8") (pintype "input"))
      (node (ref "U20") (pin "G10") (pinfunction "GND_G10") (pintype "power_in"))
      (node (ref "U20") (pin "G12") (pinfunction "GND_G12") (pintype "power_in"))
      (node (ref "U20") (pin "G14") (pinfunction "GND_G14") (pintype "power_in"))
      (node (ref "U20") (pin "G5") (pinfunction "GND_G5") (pintype "power_in"))
      (node (ref "U20") (pin "G6") (pinfunction "GND_G6") (pintype "power_in"))
      (node (ref "U20") (pin "G7") (pinfunction "GND_G7") (pintype "power_in"))
      (node (ref "U20") (pin "G8") (pinfunction "GND_G8") (pintype "power_in"))
      (node (ref "U20") (pin "G9") (pinfunction "GND_G9") (pintype "power_in"))
      (node (ref "U20") (pin "H1") (pinfunction "GND_H1") (pintype "power_in"))
      (node (ref "U20") (pin "H11") (pinfunction "GND_H11") (pintype "power_in"))
      (node (ref "U20") (pin "H21") (pinfunction "GND_H21") (pintype "power_in"))
      (node (ref "U20") (pin "H7") (pinfunction "GND_H7") (pintype "power_in"))
      (node (ref "U20") (pin "H9") (pinfunction "GND_H9") (pintype "power_in"))
      (node (ref "U20") (pin "J10") (pinfunction "GND_J10") (pintype "power_in"))
      (node (ref "U20") (pin "J12") (pinfunction "GND_J12") (pintype "power_in"))
      (node (ref "U20") (pin "J18") (pinfunction "GND_J18") (pintype "power_in"))
      (node (ref "U20") (pin "J8") (pinfunction "GND_J8") (pintype "power_in"))
      (node (ref "U20") (pin "K11") (pinfunction "GND_K11") (pintype "power_in"))
      (node (ref "U20") (pin "K15") (pinfunction "GND_K15") (pintype "power_in"))
      (node (ref "U20") (pin "K5") (pinfunction "GND_K5") (pintype "power_in"))
      (node (ref "U20") (pin "K7") (pinfunction "GND_K7") (pintype "power_in"))
      (node (ref "U20") (pin "K9") (pinfunction "GNDADC_0_K9") (pintype "power_in"))
      (node (ref "U20") (pin "L10") (pinfunction "VP_0_L10") (pintype "input"))
      (node (ref "U20") (pin "L2") (pinfunction "GND_L2") (pintype "power_in"))
      (node (ref "U20") (pin "L22") (pinfunction "GND_L22") (pintype "power_in"))
      (node (ref "U20") (pin "L8") (pinfunction "GND_L8") (pintype "power_in"))
      (node (ref "U20") (pin "L9") (pinfunction "VREFN_0_L9") (pintype "input"))
      (node (ref "U20") (pin "M10") (pinfunction "VREFP_0_M10") (pintype "input"))
      (node (ref "U20") (pin "M11") (pinfunction "GND_M11") (pintype "power_in"))
      (node (ref "U20") (pin "M19") (pinfunction "GND_M19") (pintype "power_in"))
      (node (ref "U20") (pin "M7") (pinfunction "GND_M7") (pintype "power_in"))
      (node (ref "U20") (pin "M9") (pinfunction "VN_0_M9") (pintype "input"))
      (node (ref "U20") (pin "N10") (pinfunction "DXP_0_N10") (pintype "input"))
      (node (ref "U20") (pin "N16") (pinfunction "GND_N16") (pintype "power_in"))
      (node (ref "U20") (pin "N6") (pinfunction "GND_N6") (pintype "power_in"))
      (node (ref "U20") (pin "N8") (pinfunction "GND_N8") (pintype "power_in"))
      (node (ref "U20") (pin "N9") (pinfunction "DXN_0_N9") (pintype "input"))
      (node (ref "U20") (pin "P11") (pinfunction "GND_P11") (pintype "power_in"))
      (node (ref "U20") (pin "P13") (pinfunction "GND_P13") (pintype "power_in"))
      (node (ref "U20") (pin "P3") (pinfunction "GND_P3") (pintype "power_in"))
      (node (ref "U20") (pin "P7") (pinfunction "GND_P7") (pintype "power_in"))
      (node (ref "U20") (pin "P9") (pinfunction "GND_P9") (pintype "power_in"))
      (node (ref "U20") (pin "R10") (pinfunction "GND_R10") (pintype "power_in"))
      (node (ref "U20") (pin "R12") (pinfunction "GND_R12") (pintype "power_in"))
      (node (ref "U20") (pin "R20") (pinfunction "GND_R20") (pintype "power_in"))
      (node (ref "U20") (pin "R8") (pinfunction "GND_R8") (pintype "power_in"))
      (node (ref "U20") (pin "T11") (pinfunction "GND_T11") (pintype "power_in"))
      (node (ref "U20") (pin "T17") (pinfunction "GND_T17") (pintype "power_in"))
      (node (ref "U20") (pin "T7") (pinfunction "GND_T7") (pintype "power_in"))
      (node (ref "U20") (pin "T9") (pinfunction "GND_T9") (pintype "power_in"))
      (node (ref "U20") (pin "U10") (pinfunction "M1_0_U10") (pintype "input"))
      (node (ref "U20") (pin "U14") (pinfunction "GND_U14") (pintype "power_in"))
      (node (ref "U20") (pin "U4") (pinfunction "GND_U4") (pintype "power_in"))
      (node (ref "U20") (pin "U8") (pinfunction "CFGBVS_0_U8") (pintype "input"))
      (node (ref "U20") (pin "U9") (pinfunction "M2_0_U9") (pintype "input"))
      (node (ref "U20") (pin "V1") (pinfunction "GND_V1") (pintype "power_in"))
      (node (ref "U20") (pin "V11") (pinfunction "GND_V11") (pintype "power_in"))
      (node (ref "U20") (pin "V21") (pinfunction "GND_V21") (pintype "power_in"))
      (node (ref "U20") (pin "W18") (pinfunction "GND_W18") (pintype "power_in"))
      (node (ref "U20") (pin "W8") (pinfunction "GND_W8") (pintype "power_in"))
      (node (ref "U20") (pin "Y15") (pinfunction "GND_Y15") (pintype "power_in"))
      (node (ref "U20") (pin "Y5") (pinfunction "GND_Y5") (pintype "power_in"))
      (node (ref "U40") (pin "A9") (pinfunction "VSS_A9") (pintype "power_in"))
      (node (ref "U40") (pin "B1") (pinfunction "VSSQ_B1") (pintype "power_in"))
      (node (ref "U40") (pin "B3") (pinfunction "VSS_B3") (pintype "power_in"))
      (node (ref "U40") (pin "B9") (pinfunction "VSSQ_B9") (pintype "power_in"))
      (node (ref "U40") (pin "D1") (pinfunction "VSSQ_D1") (pintype "power_in"))
      (node (ref "U40") (pin "D8") (pinfunction "VSSQ_D8") (pintype "power_in"))
      (node (ref "U40") (pin "E1") (pinfunction "VSS_E1") (pintype "power_in"))
      (node (ref "U40") (pin "E2") (pinfunction "VSSQ_E2") (pintype "power_in"))
      (node (ref "U40") (pin "E8") (pinfunction "VSSQ_E8") (pintype "power_in"))
      (node (ref "U40") (pin "F9") (pinfunction "VSSQ_F9") (pintype "power_in"))
      (node (ref "U40") (pin "G1") (pinfunction "VSSQ_G1") (pintype "power_in"))
      (node (ref "U40") (pin "G8") (pinfunction "VSS_G8") (pintype "power_in"))
      (node (ref "U40") (pin "G9") (pinfunction "VSSQ_G9") (pintype "power_in"))
      (node (ref "U40") (pin "J2") (pinfunction "VSS_J2") (pintype "power_in"))
      (node (ref "U40") (pin "J8") (pinfunction "VSS_J8") (pintype "power_in"))
      (node (ref "U40") (pin "M1") (pinfunction "VSS_M1") (pintype "power_in"))
      (node (ref "U40") (pin "M9") (pinfunction "VSS_M9") (pintype "power_in"))
      (node (ref "U40") (pin "P1") (pinfunction "VSS_P1") (pintype "power_in"))
      (node (ref "U40") (pin "P9") (pinfunction "VSS_P9") (pintype "power_in"))
      (node (ref "U40") (pin "T1") (pinfunction "VSS_T1") (pintype "power_in"))
      (node (ref "U40") (pin "T9") (pinfunction "VSS_T9") (pintype "power_in"))
      (node (ref "U41") (pin "A9") (pinfunction "VSS_A9") (pintype "power_in"))
      (node (ref "U41") (pin "B1") (pinfunction "VSSQ_B1") (pintype "power_in"))
      (node (ref "U41") (pin "B3") (pinfunction "VSS_B3") (pintype "power_in"))
      (node (ref "U41") (pin "B9") (pinfunction "VSSQ_B9") (pintype "power_in"))
      (node (ref "U41") (pin "D1") (pinfunction "VSSQ_D1") (pintype "power_in"))
      (node (ref "U41") (pin "D8") (pinfunction "VSSQ_D8") (pintype "power_in"))
      (node (ref "U41") (pin "E1") (pinfunction "VSS_E1") (pintype "power_in"))
      (node (ref "U41") (pin "E2") (pinfunction "VSSQ_E2") (pintype "power_in"))
      (node (ref "U41") (pin "E8") (pinfunction "VSSQ_E8") (pintype "power_in"))
      (node (ref "U41") (pin "F9") (pinfunction "VSSQ_F9") (pintype "power_in"))
      (node (ref "U41") (pin "G1") (pinfunction "VSSQ_G1") (pintype "power_in"))
      (node (ref "U41") (pin "G8") (pinfunction "VSS_G8") (pintype "power_in"))
      (node (ref "U41") (pin "G9") (pinfunction "VSSQ_G9") (pintype "power_in"))
      (node (ref "U41") (pin "J2") (pinfunction "VSS_J2") (pintype "power_in"))
      (node (ref "U41") (pin "J8") (pinfunction "VSS_J8") (pintype "power_in"))
      (node (ref "U41") (pin "M1") (pinfunction "VSS_M1") (pintype "power_in"))
      (node (ref "U41") (pin "M9") (pinfunction "VSS_M9") (pintype "power_in"))
      (node (ref "U41") (pin "P1") (pinfunction "VSS_P1") (pintype "power_in"))
      (node (ref "U41") (pin "P9") (pinfunction "VSS_P9") (pintype "power_in"))
      (node (ref "U41") (pin "T1") (pinfunction "VSS_T1") (pintype "power_in"))
      (node (ref "U41") (pin "T9") (pinfunction "VSS_T9") (pintype "power_in"))
      (node (ref "U44") (pin "9") (pintype "power_in"))
      (node (ref "X7") (pin "5") (pinfunction "5_5") (pintype "passive"))
    )
    (net (code "23") (name "Net-(HL11-Cathode)") (class "Default")
      (node (ref "HL11") (pin "2") (pinfunction "Cathode_2") (pintype "passive"))
      (node (ref "R202") (pin "2") (pinfunction "2_2") (pintype "passive"))
    )
    (net (code "24") (name "VIO_CAM") (class "Default")
      (node (ref "U20") (pin "A17") (pinfunction "VCCO_16_A17") (pintype "power_in"))
      (node (ref "U20") (pin "B14") (pinfunction "VCCO_16_B14") (pintype "power_in"))
      (node (ref "U20") (pin "C21") (pinfunction "VCCO_16_C21") (pintype "power_in"))
      (node (ref "U20") (pin "D18") (pinfunction "VCCO_16_D18") (pintype "power_in"))
      (node (ref "U20") (pin "E15") (pinfunction "VCCO_16_E15") (pintype "power_in"))
      (node (ref "U20") (pin "F22") (pinfunction "VCCO_16_F22") (pintype "power_in"))
    )
    (net (code "25") (name "unconnected-(C186-Pad1)") (class "Default")
      (node (ref "C186") (pin "1") (pinfunction "1_1") (pintype "passive"))
    )
    (net (code "26") (name "unconnected-(C186-Pad2)") (class "Default")
      (node (ref "C186") (pin "2") (pinfunction "2_2") (pintype "passive"))
    )
    (net (code "27") (name "unconnected-(C187-Pad1)") (class "Default")
      (node (ref "C187") (pin "1") (pinfunction "1_1") (pintype "passive"))
    )
    (net (code "28") (name "unconnected-(C187-Pad2)") (class "Default")
      (node (ref "C187") (pin "2") (pinfunction "2_2") (pintype "passive"))
    )
    (net (code "29") (name "unconnected-(C188-Pad1)") (class "Default")
      (node (ref "C188") (pin "1") (pinfunction "1_1") (pintype "passive"))
    )
    (net (code "30") (name "unconnected-(C188-Pad2)") (class "Default")
      (node (ref "C188") (pin "2") (pinfunction "2_2") (pintype "passive"))
    )
    (net (code "31") (name "unconnected-(C189-Pad1)") (class "Default")
      (node (ref "C189") (pin "1") (pinfunction "1_1") (pintype "passive"))
    )
    (net (code "32") (name "unconnected-(C189-Pad2)") (class "Default")
      (node (ref "C189") (pin "2") (pinfunction "2_2") (pintype "passive"))
    )
    (net (code "33") (name "unconnected-(C194-Pad1)") (class "Default")
      (node (ref "C194") (pin "1") (pinfunction "1_1") (pintype "passive"))
    )
    (net (code "34") (name "unconnected-(C194-Pad2)") (class "Default")
      (node (ref "C194") (pin "2") (pinfunction "2_2") (pintype "passive"))
    )
    (net (code "35") (name "unconnected-(C195-Pad1)") (class "Default")
      (node (ref "C195") (pin "1") (pinfunction "1_1") (pintype "passive"))
    )
    (net (code "36") (name "unconnected-(C195-Pad2)") (class "Default")
      (node (ref "C195") (pin "2") (pinfunction "2_2") (pintype "passive"))
    )
    (net (code "37") (name "unconnected-(C196-Pad1)") (class "Default")
      (node (ref "C196") (pin "1") (pinfunction "1_1") (pintype "passive"))
    )
    (net (code "38") (name "unconnected-(C196-Pad2)") (class "Default")
      (node (ref "C196") (pin "2") (pinfunction "2_2") (pintype "passive"))
    )
    (net (code "39") (name "unconnected-(C197-Pad1)") (class "Default")
      (node (ref "C197") (pin "1") (pinfunction "1_1") (pintype "passive"))
    )
    (net (code "40") (name "unconnected-(C197-Pad2)") (class "Default")
      (node (ref "C197") (pin "2") (pinfunction "2_2") (pintype "passive"))
    )
    (net (code "41") (name "unconnected-(U20H-MGTPTXN0_216-PadA4)") (class "Default")
      (node (ref "U20") (pin "A4") (pinfunction "MGTPTXN0_216_A4") (pintype "output"))
    )
    (net (code "42") (name "unconnected-(U20H-MGTPTXN1_216-PadC5)") (class "Default")
      (node (ref "U20") (pin "C5") (pinfunction "MGTPTXN1_216_C5") (pintype "output"))
    )
    (net (code "43") (name "unconnected-(U20H-MGTPTXN2_216-PadA6)") (class "Default")
      (node (ref "U20") (pin "A6") (pinfunction "MGTPTXN2_216_A6") (pintype "output"))
    )
    (net (code "44") (name "unconnected-(U20H-MGTPTXN3_216-PadC7)") (class "Default")
      (node (ref "U20") (pin "C7") (pinfunction "MGTPTXN3_216_C7") (pintype "output"))
    )
    (net (code "45") (name "unconnected-(U20H-MGTPTXP0_216-PadB4)") (class "Default")
      (node (ref "U20") (pin "B4") (pinfunction "MGTPTXP0_216_B4") (pintype "output"))
    )
    (net (code "46") (name "unconnected-(U20H-MGTPTXP1_216-PadD5)") (class "Default")
      (node (ref "U20") (pin "D5") (pinfunction "MGTPTXP1_216_D5") (pintype "output"))
    )
    (net (code "47") (name "unconnected-(U20H-MGTPTXP2_216-PadB6)") (class "Default")
      (node (ref "U20") (pin "B6") (pinfunction "MGTPTXP2_216_B6") (pintype "output"))
    )
    (net (code "48") (name "unconnected-(U20H-MGTPTXP3_216-PadD7)") (class "Default")
      (node (ref "U20") (pin "D7") (pinfunction "MGTPTXP3_216_D7") (pintype "output"))
    )
    (net (code "49") (name "unconnected-(U40A-NC-PadJ1)") (class "Default")
      (node (ref "U40") (pin "J1") (pinfunction "NC_J1") (pintype "passive"))
    )
    (net (code "50") (name "unconnected-(U40A-NC-PadJ9)") (class "Default")
      (node (ref "U40") (pin "J9") (pinfunction "NC_J9") (pintype "passive"))
    )
    (net (code "51") (name "unconnected-(U40A-NC-PadL1)") (class "Default")
      (node (ref "U40") (pin "L1") (pinfunction "NC_L1") (pintype "passive"))
    )
    (net (code "52") (name "unconnected-(U40A-NC-PadL9)") (class "Default")
      (node (ref "U40") (pin "L9") (pinfunction "NC_L9") (pintype "passive"))
    )
    (net (code "53") (name "unconnected-(U40A-NC-PadM7)") (class "Default")
      (node (ref "U40") (pin "M7") (pinfunction "NC_M7") (pintype "passive"))
    )
    (net (code "54") (name "unconnected-(U41A-NC-PadJ1)") (class "Default")
      (node (ref "U41") (pin "J1") (pinfunction "NC_J1") (pintype "passive"))
    )
    (net (code "55") (name "unconnected-(U41A-NC-PadJ9)") (class "Default")
      (node (ref "U41") (pin "J9") (pinfunction "NC_J9") (pintype "passive"))
    )
    (net (code "56") (name "unconnected-(U41A-NC-PadL1)") (class "Default")
      (node (ref "U41") (pin "L1") (pinfunction "NC_L1") (pintype "passive"))
    )
    (net (code "57") (name "unconnected-(U41A-NC-PadL9)") (class "Default")
      (node (ref "U41") (pin "L9") (pinfunction "NC_L9") (pintype "passive"))
    )
    (net (code "58") (name "unconnected-(U41A-NC-PadM7)") (class "Default")
      (node (ref "U41") (pin "M7") (pinfunction "NC_M7") (pintype "passive"))
    )
  )
)
